# MPU-Control.net
KiCad netlist of a schematic drawn in Altium Designer
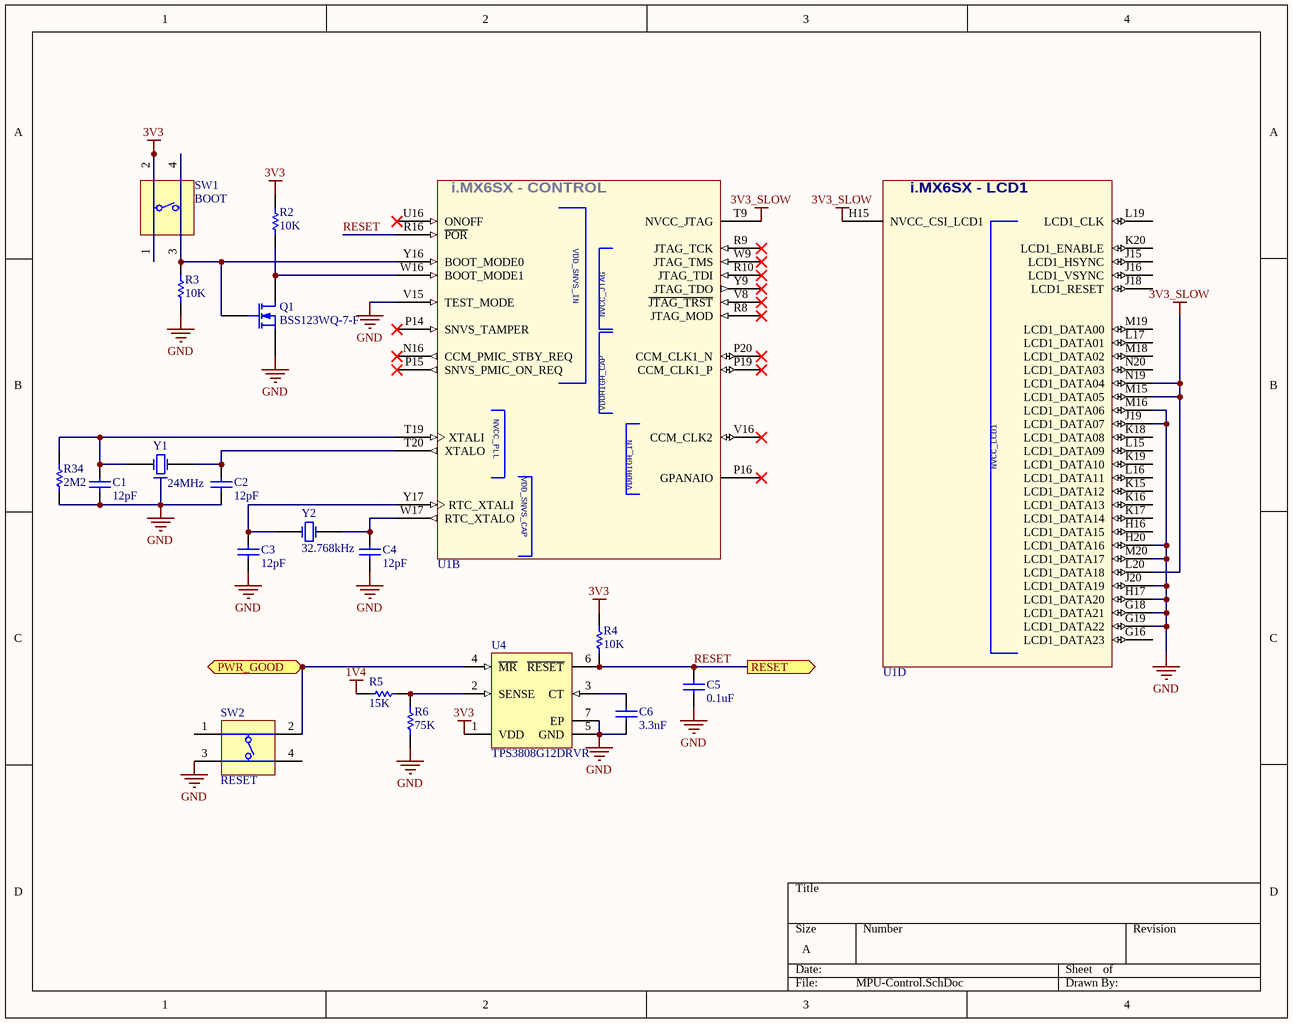
[diagram p0: MPU-Control.SchDoc]

(export (version "E")
  (design (tool "Eeschema 10.0.6"))
  (components
    (comp (ref "C1")
      (value "12pF")
      (footprint "C0402[1005X55]")
      (description "12pF 50V 5% 0402 (1005 Metric)")
      (fields (field (name "PARTNUMBER") "GRM1555C1H120JA01D") (field (name "MANUFACTURER") "Murata"))
      (libsource (lib "Capacitors") (part "CAP_12pF_50V_0402_5%"))
    )
    (comp (ref "C2")
      (value "12pF")
      (footprint "C0402[1005X55]")
      (description "12pF 50V 5% 0402 (1005 Metric)")
      (fields (field (name "PARTNUMBER") "GRM1555C1H120JA01D") (field (name "MANUFACTURER") "Murata"))
      (libsource (lib "Capacitors") (part "CAP_12pF_50V_0402_5%"))
    )
    (comp (ref "C3")
      (value "12pF")
      (footprint "C0402[1005X55]")
      (description "12pF 50V 5% 0402 (1005 Metric)")
      (fields (field (name "PARTNUMBER") "GRM1555C1H120JA01D") (field (name "MANUFACTURER") "Murata"))
      (libsource (lib "Capacitors") (part "CAP_12pF_50V_0402_5%"))
    )
    (comp (ref "C4")
      (value "12pF")
      (footprint "C0402[1005X55]")
      (description "12pF 50V 5% 0402 (1005 Metric)")
      (fields (field (name "PARTNUMBER") "GRM1555C1H120JA01D") (field (name "MANUFACTURER") "Murata"))
      (libsource (lib "Capacitors") (part "CAP_12pF_50V_0402_5%"))
    )
    (comp (ref "C5")
      (value "0.1uF")
      (footprint "C0402[1005X55]")
      (description "0.1uF 6.3V 10% 0402 (1005 Metric)")
      (fields (field (name "PARTNUMBER") "GRM155R70J104KA01D") (field (name "MANUFACTURER") "Murata"))
      (libsource (lib "Capacitors") (part "CAP_0.1uF_6.3V_0402_10%"))
    )
    (comp (ref "C6")
      (value "3.3nF")
      (footprint "C0402[1005X55]")
      (description "3.3nF 50V 10% 0402 (1005 Metric)")
      (fields (field (name "PARTNUMBER") "GRM155R71H332KA01D") (field (name "MANUFACTURER") "Murata"))
      (libsource (lib "Capacitors") (part "CAP_3.3nF_50V_0402_10%"))
    )
    (comp (ref "Q1")
      (value "BSS123WQ-7-F")
      (footprint "SOT323-3")
      (description "N-Channel MOSFET")
      (fields (field (name "MANUFACTURER") "Diodes Incorporated"))
      (libsource (lib "MOSFETs") (part "BSS123WQ-7-F"))
    )
    (comp (ref "R2")
      (value "10K")
      (footprint "R0402[1005]")
      (description "10K 0.063W 1% 0402 (1005 Metric)")
      (fields (field (name "MANUFACTURER") "KOA Speer") (field (name "PARTNUMBER") "RK73H1ETTP1002F"))
      (libsource (lib "Resistors") (part "RES_10K_0402_1%"))
    )
    (comp (ref "R3")
      (value "10K")
      (footprint "R0402[1005]")
      (description "10K 0.063W 1% 0402 (1005 Metric)")
      (fields (field (name "MANUFACTURER") "KOA Speer") (field (name "PARTNUMBER") "RK73H1ETTP1002F"))
      (libsource (lib "Resistors") (part "RES_10K_0402_1%"))
    )
    (comp (ref "R4")
      (value "10K")
      (footprint "R0402[1005]")
      (description "10K 0.063W 1% 0402 (1005 Metric)")
      (fields (field (name "MANUFACTURER") "KOA Speer") (field (name "PARTNUMBER") "RK73H1ETTP1002F"))
      (libsource (lib "Resistors") (part "RES_10K_0402_1%"))
    )
    (comp (ref "R5")
      (value "15K")
      (footprint "R0402[1005]")
      (description "15K 0.063W 1% 0402 (1005 Metric)")
      (fields (field (name "MANUFACTURER") "KOA Speer") (field (name "PARTNUMBER") "RK73H1ETTP1502F"))
      (libsource (lib "Resistors") (part "RES_15K_0402_1%"))
    )
    (comp (ref "R6")
      (value "75K")
      (footprint "R0402[1005]")
      (description "75K 0.063W 1% 0402 (1005 Metric)")
      (fields (field (name "MANUFACTURER") "KOA Speer") (field (name "PARTNUMBER") "RK73H1ETTP7502F"))
      (libsource (lib "Resistors") (part "RES_75K_0402_1%"))
    )
    (comp (ref "R34")
      (value "2M2")
      (footprint "R0402[1005]")
      (description "2M2 0.063W 1% 0402 (1005 Metric)")
      (fields (field (name "MANUFACTURER") "KOA Speer") (field (name "PARTNUMBER") "RK73H1ETTP2204F"))
      (libsource (lib "Resistors") (part "RES_2M2_0402_1%"))
    )
    (comp (ref "SW1")
      (value "BOOT")
      (footprint "SWITCH")
      (description "Switch, SPNO Push Button SMD")
      (fields
        (field (name "MANUFACTURER") "C&K Components")
        (field (name "PARTNUMBER") "PTS810 SJM 250 SMTR LFS")
      )
      (libsource (lib "") (part "DIPT-DTSM-6_1"))
    )
    (comp (ref "SW2")
      (value "RESET")
      (footprint "SWITCH")
      (description "Switch, SPNO Push Button SMD")
      (fields
        (field (name "MANUFACTURER") "C&K Components")
        (field (name "PARTNUMBER") "PTS810 SJM 250 SMTR LFS")
      )
      (libsource (lib "Components") (part "DIPT-DTSM-6"))
    )
    (comp (ref "U1")
      (value "MCIMX6X3EVO10AB")
      (footprint "BGA-400")
      (description "IC MPU I.MX6SX 1GHZ 400MAPBGA")
      (fields (field (name "MANUFACTURER") "NXP"))
      (libsource (lib "ICs") (part "MCIMX6X3EVO10AB"))
    )
    (comp (ref "U4")
      (value "TPS3808G12DRVR")
      (footprint "DRV0006A_V")
      (fields (field (name "MANUFACTURER") "Texas Instruments"))
      (libsource (lib "Altium Content Vault") (part "TI-TPS3808G12DRV6-1600X1000TP"))
    )
    (comp (ref "Y1")
      (value "24MHz")
      (footprint "CRYSTAL_2.0x1.6")
      (fields (field (name "PARTNUMBER") "FA-128 24.0000MF10Z-W3") (field (name "MANUFACTURER") "EPSON"))
      (libsource (lib "Components") (part "FA-128 24.0000MF10Z-W3"))
    )
    (comp (ref "Y2")
      (value "32.768kHz")
      (footprint "CRYSTAL_2.0x1.2")
      (fields (field (name "PARTNUMBER") "ABS06-32.768KHZ-9-1-T") (field (name "MANUFACTURER") "Abracon"))
      (libsource (lib "Components") (part "ABS06-32.768KHZ-9-1-T"))
    )
  )
  (nets
    (net (code "1") (name "/PWR_GOOD") (class "Default")
      (node (ref "SW2") (pin "2") (pinfunction "T2_2") (pintype "passive"))
      (node (ref "U4") (pin "4") (pinfunction "~{MR}_4") (pintype "input"))
    )
    (net (code "2") (name "/RESET") (class "Default")
      (node (ref "C5") (pin "2") (pinfunction "2_2") (pintype "passive"))
      (node (ref "R4") (pin "1") (pinfunction "1_1") (pintype "passive"))
      (node (ref "U1") (pin "R16") (pinfunction "~{POR}_R16") (pintype "input"))
      (node (ref "U4") (pin "6") (pinfunction "~{RESET}_6") (pintype "tri_state"))
    )
    (net (code "3") (name "1V4") (class "Default")
      (node (ref "R5") (pin "2") (pinfunction "2_2") (pintype "passive"))
    )
    (net (code "4") (name "3V3") (class "Default")
      (node (ref "R2") (pin "2") (pinfunction "2_2") (pintype "passive"))
      (node (ref "R4") (pin "2") (pinfunction "2_2") (pintype "passive"))
      (node (ref "SW1") (pin "1") (pinfunction "T1_1") (pintype "passive"))
      (node (ref "SW1") (pin "2") (pinfunction "T2_2") (pintype "passive"))
      (node (ref "U4") (pin "1") (pinfunction "VDD_1") (pintype "power_in"))
    )
    (net (code "5") (name "3V3_SLOW") (class "Default")
      (node (ref "U1") (pin "H15") (pinfunction "NVCC_CSI_LCD1_H15") (pintype "power_in"))
      (node (ref "U1") (pin "L20") (pinfunction "LCD1_DATA18_L20") (pintype "bidirectional"))
      (node (ref "U1") (pin "M15") (pinfunction "LCD1_DATA05_M15") (pintype "bidirectional"))
      (node (ref "U1") (pin "N19") (pinfunction "LCD1_DATA04_N19") (pintype "bidirectional"))
      (node (ref "U1") (pin "T9") (pinfunction "NVCC_JTAG_T9") (pintype "power_in"))
    )
    (net (code "6") (name "GND") (class "Default")
      (node (ref "C1") (pin "1") (pinfunction "1_1") (pintype "passive"))
      (node (ref "C2") (pin "1") (pinfunction "1_1") (pintype "passive"))
      (node (ref "C3") (pin "1") (pinfunction "1_1") (pintype "passive"))
      (node (ref "C4") (pin "1") (pinfunction "1_1") (pintype "passive"))
      (node (ref "C5") (pin "1") (pinfunction "1_1") (pintype "passive"))
      (node (ref "C6") (pin "1") (pinfunction "1_1") (pintype "passive"))
      (node (ref "Q1") (pin "2") (pinfunction "S_2") (pintype "passive"))
      (node (ref "R3") (pin "1") (pinfunction "1_1") (pintype "passive"))
      (node (ref "R34") (pin "1") (pinfunction "1_1") (pintype "passive"))
      (node (ref "R6") (pin "1") (pinfunction "1_1") (pintype "passive"))
      (node (ref "SW2") (pin "3") (pinfunction "T3_3") (pintype "passive"))
      (node (ref "U1") (pin "G18") (pinfunction "LCD1_DATA21_G18") (pintype "bidirectional"))
      (node (ref "U1") (pin "G19") (pinfunction "LCD1_DATA22_G19") (pintype "bidirectional"))
      (node (ref "U1") (pin "H17") (pinfunction "LCD1_DATA20_H17") (pintype "bidirectional"))
      (node (ref "U1") (pin "H20") (pinfunction "LCD1_DATA16_H20") (pintype "bidirectional"))
      (node (ref "U1") (pin "J19") (pinfunction "LCD1_DATA07_J19") (pintype "bidirectional"))
      (node (ref "U1") (pin "J20") (pinfunction "LCD1_DATA19_J20") (pintype "bidirectional"))
      (node (ref "U1") (pin "M16") (pinfunction "LCD1_DATA06_M16") (pintype "bidirectional"))
      (node (ref "U1") (pin "M20") (pinfunction "LCD1_DATA17_M20") (pintype "bidirectional"))
      (node (ref "U1") (pin "V15") (pinfunction "TEST_MODE_V15") (pintype "input"))
      (node (ref "U4") (pin "5") (pinfunction "GND_5") (pintype "power_in"))
      (node (ref "U4") (pin "7") (pinfunction "EP_7") (pintype "power_in"))
      (node (ref "Y1") (pin "2") (pinfunction "2_2") (pintype "passive"))
    )
    (net (code "7") (name "Net-(Q1-D)") (class "Default")
      (node (ref "Q1") (pin "3") (pinfunction "D_3") (pintype "passive"))
      (node (ref "R2") (pin "1") (pinfunction "1_1") (pintype "passive"))
      (node (ref "U1") (pin "W16") (pinfunction "BOOT_MODE1_W16") (pintype "input"))
    )
    (net (code "8") (name "Net-(Q1-G)") (class "Default")
      (node (ref "Q1") (pin "1") (pinfunction "G_1") (pintype "passive"))
      (node (ref "R3") (pin "2") (pinfunction "2_2") (pintype "passive"))
      (node (ref "SW1") (pin "3") (pinfunction "T3_3") (pintype "passive"))
      (node (ref "SW1") (pin "4") (pinfunction "T3_4") (pintype "passive"))
      (node (ref "U1") (pin "Y16") (pinfunction "BOOT_MODE0_Y16") (pintype "input"))
    )
    (net (code "9") (name "Net-(U1B-RTC_XTALI)") (class "Default")
      (node (ref "C3") (pin "2") (pinfunction "2_2") (pintype "passive"))
      (node (ref "U1") (pin "Y17") (pinfunction "RTC_XTALI_Y17") (pintype "input"))
      (node (ref "Y2") (pin "1") (pinfunction "X1_1") (pintype "passive"))
    )
    (net (code "10") (name "Net-(U1B-RTC_XTALO)") (class "Default")
      (node (ref "C4") (pin "2") (pinfunction "2_2") (pintype "passive"))
      (node (ref "U1") (pin "W17") (pinfunction "RTC_XTALO_W17") (pintype "output"))
      (node (ref "Y2") (pin "2") (pinfunction "X2_2") (pintype "passive"))
    )
    (net (code "11") (name "Net-(U1B-XTALI)") (class "Default")
      (node (ref "C1") (pin "2") (pinfunction "2_2") (pintype "passive"))
      (node (ref "R34") (pin "2") (pinfunction "2_2") (pintype "passive"))
      (node (ref "U1") (pin "T19") (pinfunction "XTALI_T19") (pintype "input"))
      (node (ref "Y1") (pin "1") (pinfunction "X1_1") (pintype "passive"))
    )
    (net (code "12") (name "Net-(U1B-XTALO)") (class "Default")
      (node (ref "C2") (pin "2") (pinfunction "2_2") (pintype "passive"))
      (node (ref "U1") (pin "T20") (pinfunction "XTALO_T20") (pintype "output"))
      (node (ref "Y1") (pin "3") (pinfunction "X2_3") (pintype "passive"))
    )
    (net (code "13") (name "Net-(U4-CT)") (class "Default")
      (node (ref "C6") (pin "2") (pinfunction "2_2") (pintype "passive"))
      (node (ref "U4") (pin "3") (pinfunction "CT_3") (pintype "input"))
    )
    (net (code "14") (name "Net-(U4-SENSE)") (class "Default")
      (node (ref "R5") (pin "1") (pinfunction "1_1") (pintype "passive"))
      (node (ref "R6") (pin "2") (pinfunction "2_2") (pintype "passive"))
      (node (ref "U4") (pin "2") (pinfunction "SENSE_2") (pintype "input"))
    )
    (net (code "15") (name "unconnected-(SW2-T1-Pad1)") (class "Default")
      (node (ref "SW2") (pin "1") (pinfunction "T1_1") (pintype "passive"))
    )
    (net (code "16") (name "unconnected-(SW2-T3-Pad4)") (class "Default")
      (node (ref "SW2") (pin "4") (pinfunction "T3_4") (pintype "passive"))
    )
    (net (code "17") (name "unconnected-(U1B-CCM_CLK1_N-PadP20)") (class "Default")
      (node (ref "U1") (pin "P20") (pinfunction "CCM_CLK1_N_P20") (pintype "bidirectional+no_connect"))
    )
    (net (code "18") (name "unconnected-(U1B-CCM_CLK1_P-PadP19)") (class "Default")
      (node (ref "U1") (pin "P19") (pinfunction "CCM_CLK1_P_P19") (pintype "bidirectional+no_connect"))
    )
    (net (code "19") (name "unconnected-(U1B-CCM_CLK2-PadV16)") (class "Default")
      (node (ref "U1") (pin "V16") (pinfunction "CCM_CLK2_V16") (pintype "bidirectional+no_connect"))
    )
    (net (code "20") (name "unconnected-(U1B-CCM_PMIC_STBY_REQ-PadN16)") (class "Default")
      (node (ref "U1") (pin "N16") (pinfunction "CCM_PMIC_STBY_REQ_N16") (pintype "output+no_connect"))
    )
    (net (code "21") (name "unconnected-(U1B-GPANAIO-PadP16)") (class "Default")
      (node (ref "U1") (pin "P16") (pinfunction "GPANAIO_P16") (pintype "power_in+no_connect"))
    )
    (net (code "22") (name "unconnected-(U1B-JTAG_MOD-PadR8)") (class "Default")
      (node (ref "U1") (pin "R8") (pinfunction "JTAG_MOD_R8") (pintype "input+no_connect"))
    )
    (net (code "23") (name "unconnected-(U1B-JTAG_TCK-PadR9)") (class "Default")
      (node (ref "U1") (pin "R9") (pinfunction "JTAG_TCK_R9") (pintype "input+no_connect"))
    )
    (net (code "24") (name "unconnected-(U1B-JTAG_TDI-PadR10)") (class "Default")
      (node (ref "U1") (pin "R10") (pinfunction "JTAG_TDI_R10") (pintype "input+no_connect"))
    )
    (net (code "25") (name "unconnected-(U1B-JTAG_TDO-PadY9)") (class "Default")
      (node (ref "U1") (pin "Y9") (pinfunction "JTAG_TDO_Y9") (pintype "output+no_connect"))
    )
    (net (code "26") (name "unconnected-(U1B-JTAG_TMS-PadW9)") (class "Default")
      (node (ref "U1") (pin "W9") (pinfunction "JTAG_TMS_W9") (pintype "input+no_connect"))
    )
    (net (code "27") (name "unconnected-(U1B-ONOFF-PadU16)") (class "Default")
      (node (ref "U1") (pin "U16") (pinfunction "ONOFF_U16") (pintype "input+no_connect"))
    )
    (net (code "28") (name "unconnected-(U1B-SNVS_PMIC_ON_REQ-PadP15)") (class "Default")
      (node (ref "U1") (pin "P15") (pinfunction "SNVS_PMIC_ON_REQ_P15") (pintype "output+no_connect"))
    )
    (net (code "29") (name "unconnected-(U1B-SNVS_TAMPER-PadP14)") (class "Default")
      (node (ref "U1") (pin "P14") (pinfunction "SNVS_TAMPER_P14") (pintype "input+no_connect"))
    )
    (net (code "30") (name "unconnected-(U1B-~{JTAG_TRST}-PadV8)") (class "Default")
      (node (ref "U1") (pin "V8") (pinfunction "~{JTAG_TRST}_V8") (pintype "input+no_connect"))
    )
    (net (code "31") (name "unconnected-(U1D-LCD1_CLK-PadL19)") (class "Default")
      (node (ref "U1") (pin "L19") (pinfunction "LCD1_CLK_L19") (pintype "bidirectional"))
    )
    (net (code "32") (name "unconnected-(U1D-LCD1_DATA00-PadM19)") (class "Default")
      (node (ref "U1") (pin "M19") (pinfunction "LCD1_DATA00_M19") (pintype "bidirectional"))
    )
    (net (code "33") (name "unconnected-(U1D-LCD1_DATA01-PadL17)") (class "Default")
      (node (ref "U1") (pin "L17") (pinfunction "LCD1_DATA01_L17") (pintype "bidirectional"))
    )
    (net (code "34") (name "unconnected-(U1D-LCD1_DATA02-PadM18)") (class "Default")
      (node (ref "U1") (pin "M18") (pinfunction "LCD1_DATA02_M18") (pintype "bidirectional"))
    )
    (net (code "35") (name "unconnected-(U1D-LCD1_DATA03-PadN20)") (class "Default")
      (node (ref "U1") (pin "N20") (pinfunction "LCD1_DATA03_N20") (pintype "bidirectional"))
    )
    (net (code "36") (name "unconnected-(U1D-LCD1_DATA08-PadK18)") (class "Default")
      (node (ref "U1") (pin "K18") (pinfunction "LCD1_DATA08_K18") (pintype "bidirectional"))
    )
    (net (code "37") (name "unconnected-(U1D-LCD1_DATA09-PadL15)") (class "Default")
      (node (ref "U1") (pin "L15") (pinfunction "LCD1_DATA09_L15") (pintype "bidirectional"))
    )
    (net (code "38") (name "unconnected-(U1D-LCD1_DATA10-PadK19)") (class "Default")
      (node (ref "U1") (pin "K19") (pinfunction "LCD1_DATA10_K19") (pintype "bidirectional"))
    )
    (net (code "39") (name "unconnected-(U1D-LCD1_DATA11-PadL16)") (class "Default")
      (node (ref "U1") (pin "L16") (pinfunction "LCD1_DATA11_L16") (pintype "bidirectional"))
    )
    (net (code "40") (name "unconnected-(U1D-LCD1_DATA12-PadK15)") (class "Default")
      (node (ref "U1") (pin "K15") (pinfunction "LCD1_DATA12_K15") (pintype "bidirectional"))
    )
    (net (code "41") (name "unconnected-(U1D-LCD1_DATA13-PadK16)") (class "Default")
      (node (ref "U1") (pin "K16") (pinfunction "LCD1_DATA13_K16") (pintype "bidirectional"))
    )
    (net (code "42") (name "unconnected-(U1D-LCD1_DATA14-PadK17)") (class "Default")
      (node (ref "U1") (pin "K17") (pinfunction "LCD1_DATA14_K17") (pintype "bidirectional"))
    )
    (net (code "43") (name "unconnected-(U1D-LCD1_DATA15-PadH16)") (class "Default")
      (node (ref "U1") (pin "H16") (pinfunction "LCD1_DATA15_H16") (pintype "bidirectional"))
    )
    (net (code "44") (name "unconnected-(U1D-LCD1_DATA23-PadG16)") (class "Default")
      (node (ref "U1") (pin "G16") (pinfunction "LCD1_DATA23_G16") (pintype "bidirectional"))
    )
    (net (code "45") (name "unconnected-(U1D-LCD1_ENABLE-PadK20)") (class "Default")
      (node (ref "U1") (pin "K20") (pinfunction "LCD1_ENABLE_K20") (pintype "bidirectional"))
    )
    (net (code "46") (name "unconnected-(U1D-LCD1_HSYNC-PadJ15)") (class "Default")
      (node (ref "U1") (pin "J15") (pinfunction "LCD1_HSYNC_J15") (pintype "bidirectional"))
    )
    (net (code "47") (name "unconnected-(U1D-LCD1_RESET-PadJ18)") (class "Default")
      (node (ref "U1") (pin "J18") (pinfunction "LCD1_RESET_J18") (pintype "bidirectional"))
    )
    (net (code "48") (name "unconnected-(U1D-LCD1_VSYNC-PadJ16)") (class "Default")
      (node (ref "U1") (pin "J16") (pinfunction "LCD1_VSYNC_J16") (pintype "bidirectional"))
    )
  )
)
